# WifiTracker.net
KiCad netlist of a schematic drawn in EAGLE
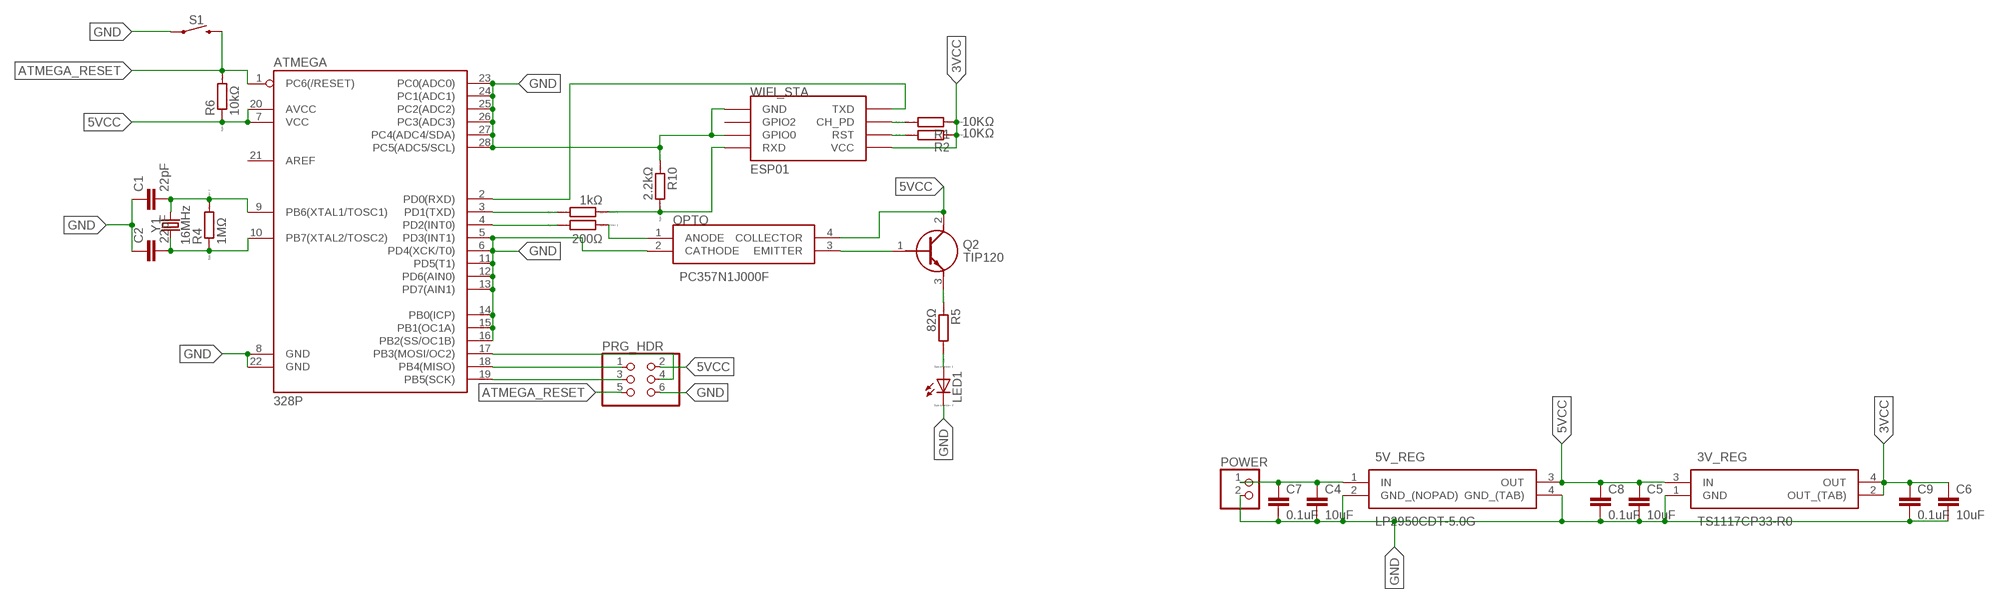
[diagram p0: schematic, sheet 1]

(export (version "E")
  (design (tool "Eeschema 10.0.6"))
  (components
    (comp (ref "3V_REG")
      (value "TS1117CP33-R0")
      (footprint "eagle-import:TO229P990X238-4N")
      (fields
        (field (name "MANUFACTURER_PART_NUMBER") "LP2950CDT-5.0G")
        (field (name "MOUSER_PART_NUMBER") "863-LP2950CDT-5.0G")
        (field (name "RS_PART_NUMBER") "0463593P")
      )
      (libsource (lib "eagle-import") (part "TS1117CP33-R0"))
    )
    (comp (ref "5V_REG")
      (value "LP2950CDT-5.0G")
      (footprint "eagle-import:TO229P990X238-4N")
      (fields
        (field (name "MOUSER_PART_NUMBER") "863-LP2950CDT-5.0G")
        (field (name "RS_PART_NUMBER") "0463593P")
      )
      (libsource (lib "eagle-import") (part "LP2950CDT-5.0G"))
    )
    (comp (ref "ATMEGA")
      (value "328P")
      (footprint "eagle-import:DIP28")
      (libsource (lib "eagle-import") (part "ATMEGA328P_PDIP"))
    )
    (comp (ref "C1")
      (value "22pF")
      (footprint "eagle-import:1206")
      (libsource (lib "eagle-import") (part "1.0UF-1206-50V-10%"))
    )
    (comp (ref "C2")
      (value "22pF")
      (footprint "eagle-import:1206")
      (libsource (lib "eagle-import") (part "1.0UF-1206-50V-10%"))
    )
    (comp (ref "C4")
      (value "10uF")
      (footprint "eagle-import:1206")
      (libsource (lib "eagle-import") (part "1.0UF-1206-50V-10%"))
    )
    (comp (ref "C5")
      (value "10uF")
      (footprint "eagle-import:1206")
      (libsource (lib "eagle-import") (part "1.0UF-1206-50V-10%"))
    )
    (comp (ref "C6")
      (value "10uF")
      (footprint "eagle-import:1206")
      (libsource (lib "eagle-import") (part "1.0UF-1206-50V-10%"))
    )
    (comp (ref "C7")
      (value "0.1uF")
      (footprint "eagle-import:1206")
      (libsource (lib "eagle-import") (part "1.0UF-1206-50V-10%"))
    )
    (comp (ref "C8")
      (value "0.1uF")
      (footprint "eagle-import:1206")
      (libsource (lib "eagle-import") (part "1.0UF-1206-50V-10%"))
    )
    (comp (ref "C9")
      (value "0.1uF")
      (footprint "eagle-import:1206")
      (libsource (lib "eagle-import") (part "1.0UF-1206-50V-10%"))
    )
    (comp (ref "LED1")
      (value "LED_ELD260")
      (footprint "eagle-import:LED_LD260")
      (libsource (lib "eagle-import") (part "LED_ELD260"))
    )
    (comp (ref "OPTO")
      (value "PC357N1J000F")
      (footprint "eagle-import:SOP254P675X300-4N")
      (fields
        (field (name "MOUSER_PART_NUMBER") "852-PC357N1J000F")
        (field (name "RS_PART_NUMBER") "1460767")
      )
      (libsource (lib "eagle-import") (part "PC357N1J000F"))
    )
    (comp (ref "POWER")
      (value "PINHD-1X2")
      (footprint "eagle-import:1X02")
      (libsource (lib "eagle-import") (part "PINHD-1X2"))
    )
    (comp (ref "PRG_HDR")
      (value "PINHD-2X3")
      (footprint "eagle-import:2X03")
      (libsource (lib "eagle-import") (part "PINHD-2X3"))
    )
    (comp (ref "Q2")
      (value "TIP120")
      (footprint "eagle-import:TO220")
      (fields (field (name "MOUSER_PART_NUMBER") "512-TIP120"))
      (libsource (lib "eagle-import") (part "TIP120"))
    )
    (comp (ref "R1")
      (value "10KΩ")
      (footprint "eagle-import:R1210")
      (libsource (lib "eagle-import") (part "RR1210"))
    )
    (comp (ref "R2")
      (value "10KΩ")
      (footprint "eagle-import:R1210")
      (libsource (lib "eagle-import") (part "RR1210"))
    )
    (comp (ref "R3")
      (value "200Ω")
      (footprint "eagle-import:R1210")
      (libsource (lib "eagle-import") (part "RR1210"))
    )
    (comp (ref "R4")
      (value "1MΩ")
      (footprint "eagle-import:R1210")
      (libsource (lib "eagle-import") (part "RR1210"))
    )
    (comp (ref "R5")
      (value "82Ω")
      (footprint "eagle-import:R1210")
      (libsource (lib "eagle-import") (part "RR1210"))
    )
    (comp (ref "R6")
      (value "10kΩ")
      (footprint "eagle-import:R1210")
      (libsource (lib "eagle-import") (part "RR1210"))
    )
    (comp (ref "R9")
      (value "1kΩ")
      (footprint "eagle-import:R1210")
      (libsource (lib "eagle-import") (part "RR1210"))
    )
    (comp (ref "R10")
      (value "2.2kΩ")
      (footprint "eagle-import:R1210")
      (libsource (lib "eagle-import") (part "RR1210"))
    )
    (comp (ref "S1")
      (value "MOMENTARY-SWITCH-SPST-PTH-6.0MM")
      (footprint "eagle-import:TACTILE_SWITCH_PTH_6.0MM")
      (libsource (lib "eagle-import") (part "MOMENTARY-SWITCH-SPST-PTH-6.0MM"))
    )
    (comp (ref "WIFI_STA")
      (value "ESP01")
      (footprint "eagle-import:ESP01")
      (libsource (lib "eagle-import") (part "ESP01"))
    )
    (comp (ref "Y1")
      (value "16MHz")
      (footprint "eagle-import:HC49UP")
      (libsource (lib "eagle-import") (part "CRYSTAL-8MHZSMD-HC49UP"))
    )
  )
  (nets
    (net (code "1") (name "3VCC") (class "Default")
      (node (ref "3V_REG") (pin "2") (pinfunction "OUT_(TAB)_2") (pintype "output"))
      (node (ref "3V_REG") (pin "4") (pinfunction "OUT_4") (pintype "output"))
      (node (ref "C6") (pin "1") (pinfunction "1_1") (pintype "passive"))
      (node (ref "C9") (pin "1") (pinfunction "1_1") (pintype "passive"))
      (node (ref "R1") (pin "1") (pinfunction "1_1") (pintype "passive"))
      (node (ref "R2") (pin "1") (pinfunction "1_1") (pintype "passive"))
      (node (ref "WIFI_STA") (pin "VCC") (pinfunction "VCC_VCC") (pintype "bidirectional"))
    )
    (net (code "2") (name "5VCC") (class "Default")
      (node (ref "3V_REG") (pin "3") (pinfunction "IN_3") (pintype "input"))
      (node (ref "5V_REG") (pin "3") (pinfunction "OUT_3") (pintype "output"))
      (node (ref "ATMEGA") (pin "20") (pinfunction "AVCC_20") (pintype "bidirectional"))
      (node (ref "ATMEGA") (pin "7") (pinfunction "VCC_7") (pintype "bidirectional"))
      (node (ref "C5") (pin "1") (pinfunction "1_1") (pintype "passive"))
      (node (ref "C8") (pin "1") (pinfunction "1_1") (pintype "passive"))
      (node (ref "OPTO") (pin "4") (pinfunction "COLLECTOR_4") (pintype "bidirectional"))
      (node (ref "PRG_HDR") (pin "2") (pinfunction "2_2") (pintype "passive"))
      (node (ref "Q2") (pin "2") (pinfunction "C_2") (pintype "bidirectional"))
      (node (ref "R6") (pin "1") (pinfunction "1_1") (pintype "passive"))
    )
    (net (code "3") (name "ATMEGA_RESET") (class "Default")
      (node (ref "ATMEGA") (pin "1") (pinfunction "PC6(/RESET)_1") (pintype "bidirectional"))
      (node (ref "PRG_HDR") (pin "5") (pinfunction "5_5") (pintype "passive"))
      (node (ref "R6") (pin "2") (pinfunction "2_2") (pintype "passive"))
      (node (ref "S1") (pin "3") (pinfunction "2_3") (pintype "passive"))
    )
    (net (code "4") (name "GND") (class "Default")
      (node (ref "3V_REG") (pin "1") (pinfunction "GND_1") (pintype "power_in"))
      (node (ref "5V_REG") (pin "2") (pinfunction "GND_(NOPAD)_2") (pintype "power_in"))
      (node (ref "5V_REG") (pin "4") (pinfunction "GND_(TAB)_4") (pintype "power_in"))
      (node (ref "ATMEGA") (pin "11") (pinfunction "PD5(T1)_11") (pintype "bidirectional"))
      (node (ref "ATMEGA") (pin "12") (pinfunction "PD6(AIN0)_12") (pintype "bidirectional"))
      (node (ref "ATMEGA") (pin "13") (pinfunction "PD7(AIN1)_13") (pintype "bidirectional"))
      (node (ref "ATMEGA") (pin "14") (pinfunction "PB0(ICP)_14") (pintype "bidirectional"))
      (node (ref "ATMEGA") (pin "15") (pinfunction "PB1(OC1A)_15") (pintype "bidirectional"))
      (node (ref "ATMEGA") (pin "16") (pinfunction "PB2(SS/OC1B)_16") (pintype "bidirectional"))
      (node (ref "ATMEGA") (pin "22") (pinfunction "GND_22") (pintype "bidirectional"))
      (node (ref "ATMEGA") (pin "23") (pinfunction "PC0(ADC0)_23") (pintype "bidirectional"))
      (node (ref "ATMEGA") (pin "24") (pinfunction "PC1(ADC1)_24") (pintype "bidirectional"))
      (node (ref "ATMEGA") (pin "25") (pinfunction "PC2(ADC2)_25") (pintype "bidirectional"))
      (node (ref "ATMEGA") (pin "26") (pinfunction "PC3(ADC3)_26") (pintype "bidirectional"))
      (node (ref "ATMEGA") (pin "27") (pinfunction "PC4(ADC4/SDA)_27") (pintype "bidirectional"))
      (node (ref "ATMEGA") (pin "28") (pinfunction "PC5(ADC5/SCL)_28") (pintype "bidirectional"))
      (node (ref "ATMEGA") (pin "5") (pinfunction "PD3(INT1)_5") (pintype "bidirectional"))
      (node (ref "ATMEGA") (pin "6") (pinfunction "PD4(XCK/T0)_6") (pintype "bidirectional"))
      (node (ref "ATMEGA") (pin "8") (pinfunction "GND_8") (pintype "bidirectional"))
      (node (ref "C1") (pin "1") (pinfunction "1_1") (pintype "passive"))
      (node (ref "C2") (pin "1") (pinfunction "1_1") (pintype "passive"))
      (node (ref "C4") (pin "2") (pinfunction "2_2") (pintype "passive"))
      (node (ref "C5") (pin "2") (pinfunction "2_2") (pintype "passive"))
      (node (ref "C6") (pin "2") (pinfunction "2_2") (pintype "passive"))
      (node (ref "C7") (pin "2") (pinfunction "2_2") (pintype "passive"))
      (node (ref "C8") (pin "2") (pinfunction "2_2") (pintype "passive"))
      (node (ref "C9") (pin "2") (pinfunction "2_2") (pintype "passive"))
      (node (ref "LED1") (pin "K") (pinfunction "C_K") (pintype "passive"))
      (node (ref "OPTO") (pin "2") (pinfunction "CATHODE_2") (pintype "bidirectional"))
      (node (ref "POWER") (pin "2") (pinfunction "2_2") (pintype "passive"))
      (node (ref "PRG_HDR") (pin "6") (pinfunction "6_6") (pintype "passive"))
      (node (ref "R10") (pin "1") (pinfunction "1_1") (pintype "passive"))
      (node (ref "S1") (pin "1") (pinfunction "1_1") (pintype "passive"))
      (node (ref "WIFI_STA") (pin "GND") (pinfunction "GND_GND") (pintype "bidirectional"))
      (node (ref "WIFI_STA") (pin "GPIO0") (pinfunction "GPIO0_GPIO0") (pintype "bidirectional"))
    )
    (net (code "5") (name "Net-(5V_REG-IN)") (class "Default")
      (node (ref "5V_REG") (pin "1") (pinfunction "IN_1") (pintype "input"))
      (node (ref "C4") (pin "1") (pinfunction "1_1") (pintype "passive"))
      (node (ref "C7") (pin "1") (pinfunction "1_1") (pintype "passive"))
      (node (ref "POWER") (pin "1") (pinfunction "1_1") (pintype "passive"))
    )
    (net (code "6") (name "Net-(ATMEGA-PB3(MOSI{slash}OC2))") (class "Default")
      (node (ref "ATMEGA") (pin "17") (pinfunction "PB3(MOSI/OC2)_17") (pintype "bidirectional"))
      (node (ref "PRG_HDR") (pin "4") (pinfunction "4_4") (pintype "passive"))
    )
    (net (code "7") (name "Net-(ATMEGA-PB4(MISO))") (class "Default")
      (node (ref "ATMEGA") (pin "18") (pinfunction "PB4(MISO)_18") (pintype "bidirectional"))
      (node (ref "PRG_HDR") (pin "1") (pinfunction "1_1") (pintype "passive"))
    )
    (net (code "8") (name "Net-(ATMEGA-PB5(SCK))") (class "Default")
      (node (ref "ATMEGA") (pin "19") (pinfunction "PB5(SCK)_19") (pintype "bidirectional"))
      (node (ref "PRG_HDR") (pin "3") (pinfunction "3_3") (pintype "passive"))
    )
    (net (code "9") (name "Net-(ATMEGA-PB6(XTAL1{slash}TOSC1))") (class "Default")
      (node (ref "ATMEGA") (pin "9") (pinfunction "PB6(XTAL1/TOSC1)_9") (pintype "bidirectional"))
      (node (ref "C1") (pin "2") (pinfunction "2_2") (pintype "passive"))
      (node (ref "R4") (pin "2") (pinfunction "2_2") (pintype "passive"))
      (node (ref "Y1") (pin "2") (pinfunction "2_2") (pintype "passive"))
    )
    (net (code "10") (name "Net-(ATMEGA-PB7(XTAL2{slash}TOSC2))") (class "Default")
      (node (ref "ATMEGA") (pin "10") (pinfunction "PB7(XTAL2/TOSC2)_10") (pintype "bidirectional"))
      (node (ref "C2") (pin "2") (pinfunction "2_2") (pintype "passive"))
      (node (ref "R4") (pin "1") (pinfunction "1_1") (pintype "passive"))
      (node (ref "Y1") (pin "1") (pinfunction "1_1") (pintype "passive"))
    )
    (net (code "11") (name "Net-(ATMEGA-PD0(RXD))") (class "Default")
      (node (ref "ATMEGA") (pin "2") (pinfunction "PD0(RXD)_2") (pintype "bidirectional"))
      (node (ref "WIFI_STA") (pin "TX") (pinfunction "TXD_TX") (pintype "bidirectional"))
    )
    (net (code "12") (name "Net-(ATMEGA-PD1(TXD))") (class "Default")
      (node (ref "ATMEGA") (pin "3") (pinfunction "PD1(TXD)_3") (pintype "bidirectional"))
      (node (ref "R9") (pin "2") (pinfunction "2_2") (pintype "passive"))
    )
    (net (code "13") (name "Net-(ATMEGA-PD2(INT0))") (class "Default")
      (node (ref "ATMEGA") (pin "4") (pinfunction "PD2(INT0)_4") (pintype "bidirectional"))
      (node (ref "R3") (pin "2") (pinfunction "2_2") (pintype "passive"))
    )
    (net (code "14") (name "Net-(LED1-PadA)") (class "Default")
      (node (ref "LED1") (pin "A") (pinfunction "A_A") (pintype "passive"))
      (node (ref "R5") (pin "2") (pinfunction "2_2") (pintype "passive"))
    )
    (net (code "15") (name "Net-(OPTO-ANODE)") (class "Default")
      (node (ref "OPTO") (pin "1") (pinfunction "ANODE_1") (pintype "bidirectional"))
      (node (ref "R3") (pin "1") (pinfunction "1_1") (pintype "passive"))
    )
    (net (code "16") (name "Net-(OPTO-EMITTER)") (class "Default")
      (node (ref "OPTO") (pin "3") (pinfunction "EMITTER_3") (pintype "bidirectional"))
      (node (ref "Q2") (pin "1") (pinfunction "B_1") (pintype "bidirectional"))
    )
    (net (code "17") (name "Net-(Q2-E)") (class "Default")
      (node (ref "Q2") (pin "3") (pinfunction "E_3") (pintype "bidirectional"))
      (node (ref "R5") (pin "1") (pinfunction "1_1") (pintype "passive"))
    )
    (net (code "18") (name "Net-(R1-Pad2)") (class "Default")
      (node (ref "R1") (pin "2") (pinfunction "2_2") (pintype "passive"))
      (node (ref "WIFI_STA") (pin "CH_PD") (pinfunction "CH_PD_CH_PD") (pintype "bidirectional"))
    )
    (net (code "19") (name "Net-(R2-Pad2)") (class "Default")
      (node (ref "R2") (pin "2") (pinfunction "2_2") (pintype "passive"))
      (node (ref "WIFI_STA") (pin "RST") (pinfunction "RST_RST") (pintype "bidirectional"))
    )
    (net (code "20") (name "Net-(WIFI_STA-RXD)") (class "Default")
      (node (ref "R10") (pin "2") (pinfunction "2_2") (pintype "passive"))
      (node (ref "R9") (pin "1") (pinfunction "1_1") (pintype "passive"))
      (node (ref "WIFI_STA") (pin "RX") (pinfunction "RXD_RX") (pintype "bidirectional"))
    )
    (net (code "21") (name "unconnected-(ATMEGA-AREF-Pad21)") (class "Default")
      (node (ref "ATMEGA") (pin "21") (pinfunction "AREF_21") (pintype "bidirectional"))
    )
    (net (code "22") (name "unconnected-(WIFI_STA-PadGPIO2)") (class "Default")
      (node (ref "WIFI_STA") (pin "GPIO2") (pinfunction "GPIO2_GPIO2") (pintype "bidirectional"))
    )
  )
)
